# Varela-Logical_EPS_v_1_0.net
KiCad netlist of a schematic drawn in EAGLE
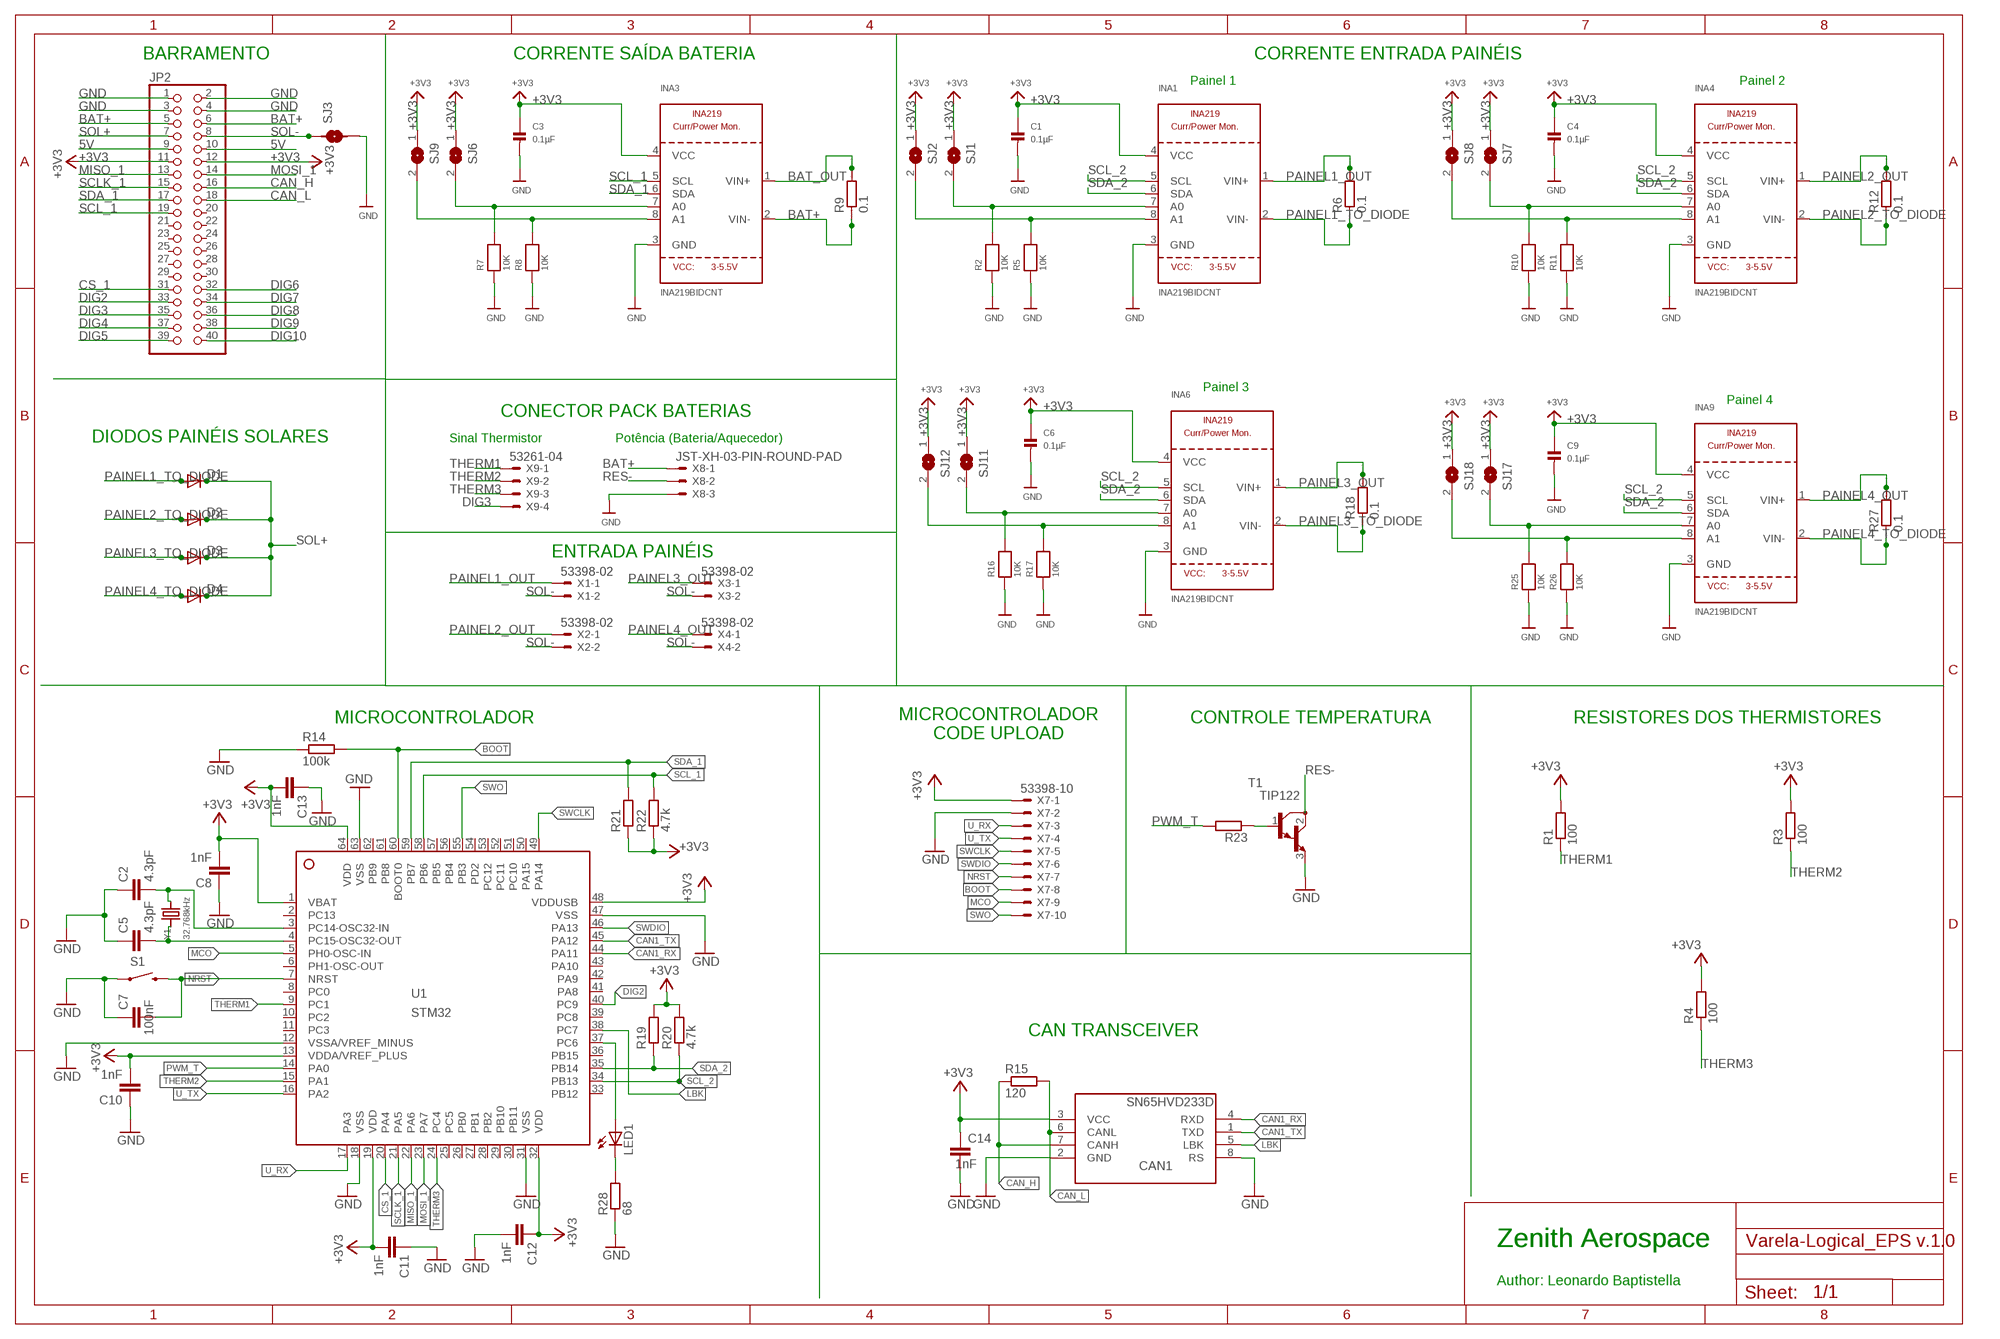
[diagram p0: schematic, sheet 1]

(export (version "E")
  (design (tool "Eeschema 10.0.6"))
  (components
    (comp (ref "C1")
      (value "0.1µF")
      (footprint "eagle-import:1206")
      (libsource (lib "eagle-import") (part "CAP_CERAMIC1206"))
    )
    (comp (ref "C2")
      (value "4.3pF")
      (footprint "eagle-import:C1206")
      (libsource (lib "eagle-import") (part "C-EUC1206"))
    )
    (comp (ref "C3")
      (value "0.1µF")
      (footprint "eagle-import:1206")
      (libsource (lib "eagle-import") (part "CAP_CERAMIC1206"))
    )
    (comp (ref "C4")
      (value "0.1µF")
      (footprint "eagle-import:1206")
      (libsource (lib "eagle-import") (part "CAP_CERAMIC1206"))
    )
    (comp (ref "C5")
      (value "4.3pF")
      (footprint "eagle-import:C1206")
      (libsource (lib "eagle-import") (part "C-EUC1206"))
    )
    (comp (ref "C6")
      (value "0.1µF")
      (footprint "eagle-import:1206")
      (libsource (lib "eagle-import") (part "CAP_CERAMIC1206"))
    )
    (comp (ref "C7")
      (value "100nF")
      (footprint "eagle-import:C1206")
      (libsource (lib "eagle-import") (part "C-EUC1206"))
    )
    (comp (ref "C8")
      (value "1nF")
      (footprint "eagle-import:C1206")
      (libsource (lib "eagle-import") (part "C-EUC1206"))
    )
    (comp (ref "C9")
      (value "0.1µF")
      (footprint "eagle-import:1206")
      (libsource (lib "eagle-import") (part "CAP_CERAMIC1206"))
    )
    (comp (ref "C10")
      (value "1nF")
      (footprint "eagle-import:C1206")
      (libsource (lib "eagle-import") (part "C-EUC1206"))
    )
    (comp (ref "C11")
      (value "1nF")
      (footprint "eagle-import:C1206")
      (libsource (lib "eagle-import") (part "C-EUC1206"))
    )
    (comp (ref "C12")
      (value "1nF")
      (footprint "eagle-import:C1206")
      (libsource (lib "eagle-import") (part "C-EUC1206"))
    )
    (comp (ref "C13")
      (value "1nF")
      (footprint "eagle-import:C1206")
      (libsource (lib "eagle-import") (part "C-EUC1206"))
    )
    (comp (ref "C14")
      (value "1nF")
      (footprint "eagle-import:C1206")
      (libsource (lib "eagle-import") (part "C-EUC1206"))
    )
    (comp (ref "CAN1")
      (value "SN65HVD233D")
      (footprint "eagle-import:SOIC8")
      (fields (field (name "MF") "Texas Instruments"))
      (libsource (lib "eagle-import") (part "SN65HVD233D"))
    )
    (comp (ref "D1")
      (value "DIODE-DO-214AC")
      (footprint "eagle-import:DO-214AC")
      (libsource (lib "eagle-import") (part "DIODE-DO-214AC"))
    )
    (comp (ref "D2")
      (value "DIODE-DO-214AC")
      (footprint "eagle-import:DO-214AC")
      (libsource (lib "eagle-import") (part "DIODE-DO-214AC"))
    )
    (comp (ref "D3")
      (value "DIODE-DO-214AC")
      (footprint "eagle-import:DO-214AC")
      (libsource (lib "eagle-import") (part "DIODE-DO-214AC"))
    )
    (comp (ref "D4")
      (value "DIODE-DO-214AC")
      (footprint "eagle-import:DO-214AC")
      (libsource (lib "eagle-import") (part "DIODE-DO-214AC"))
    )
    (comp (ref "INA1")
      (value "INA219BIDCNT")
      (footprint "eagle-import:SOT23-8")
      (libsource (lib "eagle-import") (part "INA219"))
    )
    (comp (ref "INA3")
      (value "INA219BIDCNT")
      (footprint "eagle-import:SOT23-8")
      (libsource (lib "eagle-import") (part "INA219"))
    )
    (comp (ref "INA4")
      (value "INA219BIDCNT")
      (footprint "eagle-import:SOT23-8")
      (libsource (lib "eagle-import") (part "INA219"))
    )
    (comp (ref "INA6")
      (value "INA219BIDCNT")
      (footprint "eagle-import:SOT23-8")
      (libsource (lib "eagle-import") (part "INA219"))
    )
    (comp (ref "INA9")
      (value "INA219BIDCNT")
      (footprint "eagle-import:SOT23-8")
      (libsource (lib "eagle-import") (part "INA219"))
    )
    (comp (ref "JP2")
      (value "PINHD-2X20")
      (footprint "eagle-import:2X20")
      (libsource (lib "eagle-import") (part "PINHD-2X20"))
    )
    (comp (ref "LED1")
      (value "LEDSMT1206")
      (footprint "eagle-import:1206")
      (libsource (lib "eagle-import") (part "LEDSMT1206"))
    )
    (comp (ref "R1")
      (value "100")
      (footprint "eagle-import:R1206")
      (libsource (lib "eagle-import") (part "R-EU_R1206"))
    )
    (comp (ref "R2")
      (value "10K")
      (footprint "eagle-import:1206")
      (libsource (lib "eagle-import") (part "RESISTOR1206"))
    )
    (comp (ref "R3")
      (value "100")
      (footprint "eagle-import:R1206")
      (libsource (lib "eagle-import") (part "R-EU_R1206"))
    )
    (comp (ref "R4")
      (value "100")
      (footprint "eagle-import:R1206")
      (libsource (lib "eagle-import") (part "R-EU_R1206"))
    )
    (comp (ref "R5")
      (value "10K")
      (footprint "eagle-import:1206")
      (libsource (lib "eagle-import") (part "RESISTOR1206"))
    )
    (comp (ref "R6")
      (value "0.1")
      (footprint "eagle-import:R2512")
      (libsource (lib "eagle-import") (part "RR2512"))
    )
    (comp (ref "R7")
      (value "10K")
      (footprint "eagle-import:1206")
      (libsource (lib "eagle-import") (part "RESISTOR1206"))
    )
    (comp (ref "R8")
      (value "10K")
      (footprint "eagle-import:1206")
      (libsource (lib "eagle-import") (part "RESISTOR1206"))
    )
    (comp (ref "R9")
      (value "0.1")
      (footprint "eagle-import:R2512")
      (libsource (lib "eagle-import") (part "RR2512"))
    )
    (comp (ref "R10")
      (value "10K")
      (footprint "eagle-import:1206")
      (libsource (lib "eagle-import") (part "RESISTOR1206"))
    )
    (comp (ref "R11")
      (value "10K")
      (footprint "eagle-import:1206")
      (libsource (lib "eagle-import") (part "RESISTOR1206"))
    )
    (comp (ref "R12")
      (value "0.1")
      (footprint "eagle-import:R2512")
      (libsource (lib "eagle-import") (part "RR2512"))
    )
    (comp (ref "R14")
      (value "100k")
      (footprint "eagle-import:R1206")
      (libsource (lib "eagle-import") (part "R-EU_R1206"))
    )
    (comp (ref "R15")
      (value "120")
      (footprint "eagle-import:R1206")
      (libsource (lib "eagle-import") (part "R-EU_R1206"))
    )
    (comp (ref "R16")
      (value "10K")
      (footprint "eagle-import:1206")
      (libsource (lib "eagle-import") (part "RESISTOR1206"))
    )
    (comp (ref "R17")
      (value "10K")
      (footprint "eagle-import:1206")
      (libsource (lib "eagle-import") (part "RESISTOR1206"))
    )
    (comp (ref "R18")
      (value "0.1")
      (footprint "eagle-import:R2512")
      (libsource (lib "eagle-import") (part "RR2512"))
    )
    (comp (ref "R19")
      (value "4.7k")
      (footprint "eagle-import:R1206")
      (libsource (lib "eagle-import") (part "R-EU_R1206"))
    )
    (comp (ref "R20")
      (value "4.7k")
      (footprint "eagle-import:R1206")
      (libsource (lib "eagle-import") (part "R-EU_R1206"))
    )
    (comp (ref "R21")
      (value "4.7k")
      (footprint "eagle-import:R1206")
      (libsource (lib "eagle-import") (part "R-EU_R1206"))
    )
    (comp (ref "R22")
      (value "4.7k")
      (footprint "eagle-import:R1206")
      (libsource (lib "eagle-import") (part "R-EU_R1206"))
    )
    (comp (ref "R23")
      (value "R-EU_R1206")
      (footprint "eagle-import:R1206")
      (libsource (lib "eagle-import") (part "R-EU_R1206"))
    )
    (comp (ref "R25")
      (value "10K")
      (footprint "eagle-import:1206")
      (libsource (lib "eagle-import") (part "RESISTOR1206"))
    )
    (comp (ref "R26")
      (value "10K")
      (footprint "eagle-import:1206")
      (libsource (lib "eagle-import") (part "RESISTOR1206"))
    )
    (comp (ref "R27")
      (value "0.1")
      (footprint "eagle-import:R2512")
      (libsource (lib "eagle-import") (part "RR2512"))
    )
    (comp (ref "R28")
      (value "68")
      (footprint "eagle-import:R1206")
      (libsource (lib "eagle-import") (part "R-EU_R1206"))
    )
    (comp (ref "S1")
      (value "SWITCH-MOMENTARY-2SMD-1101NE")
      (footprint "eagle-import:TACTILE-SWITCH-1101NE")
      (libsource (lib "eagle-import") (part "SWITCH-MOMENTARY-2SMD-1101NE"))
    )
    (comp (ref "SJ1")
      (value "SOLDERJUMPERREFLOW_NOPASTE")
      (footprint "eagle-import:SOLDERJUMPER_REFLOW_NOPASTE")
      (libsource (lib "eagle-import") (part "SOLDERJUMPERREFLOW_NOPASTE"))
    )
    (comp (ref "SJ2")
      (value "SOLDERJUMPERREFLOW_NOPASTE")
      (footprint "eagle-import:SOLDERJUMPER_REFLOW_NOPASTE")
      (libsource (lib "eagle-import") (part "SOLDERJUMPERREFLOW_NOPASTE"))
    )
    (comp (ref "SJ3")
      (value "SMD-JUMPER-2")
      (footprint "eagle-import:SMD-JUMPER-2")
      (libsource (lib "eagle-import") (part "SMD-JUMPER-2"))
    )
    (comp (ref "SJ6")
      (value "SOLDERJUMPERREFLOW_NOPASTE")
      (footprint "eagle-import:SOLDERJUMPER_REFLOW_NOPASTE")
      (libsource (lib "eagle-import") (part "SOLDERJUMPERREFLOW_NOPASTE"))
    )
    (comp (ref "SJ7")
      (value "SOLDERJUMPERREFLOW_NOPASTE")
      (footprint "eagle-import:SOLDERJUMPER_REFLOW_NOPASTE")
      (libsource (lib "eagle-import") (part "SOLDERJUMPERREFLOW_NOPASTE"))
    )
    (comp (ref "SJ8")
      (value "SOLDERJUMPERREFLOW_NOPASTE")
      (footprint "eagle-import:SOLDERJUMPER_REFLOW_NOPASTE")
      (libsource (lib "eagle-import") (part "SOLDERJUMPERREFLOW_NOPASTE"))
    )
    (comp (ref "SJ9")
      (value "SOLDERJUMPERREFLOW_NOPASTE")
      (footprint "eagle-import:SOLDERJUMPER_REFLOW_NOPASTE")
      (libsource (lib "eagle-import") (part "SOLDERJUMPERREFLOW_NOPASTE"))
    )
    (comp (ref "SJ11")
      (value "SOLDERJUMPERREFLOW_NOPASTE")
      (footprint "eagle-import:SOLDERJUMPER_REFLOW_NOPASTE")
      (libsource (lib "eagle-import") (part "SOLDERJUMPERREFLOW_NOPASTE"))
    )
    (comp (ref "SJ12")
      (value "SOLDERJUMPERREFLOW_NOPASTE")
      (footprint "eagle-import:SOLDERJUMPER_REFLOW_NOPASTE")
      (libsource (lib "eagle-import") (part "SOLDERJUMPERREFLOW_NOPASTE"))
    )
    (comp (ref "SJ17")
      (value "SOLDERJUMPERREFLOW_NOPASTE")
      (footprint "eagle-import:SOLDERJUMPER_REFLOW_NOPASTE")
      (libsource (lib "eagle-import") (part "SOLDERJUMPERREFLOW_NOPASTE"))
    )
    (comp (ref "SJ18")
      (value "SOLDERJUMPERREFLOW_NOPASTE")
      (footprint "eagle-import:SOLDERJUMPER_REFLOW_NOPASTE")
      (libsource (lib "eagle-import") (part "SOLDERJUMPERREFLOW_NOPASTE"))
    )
    (comp (ref "T1")
      (value "TIP122")
      (footprint "eagle-import:TO220")
      (libsource (lib "eagle-import") (part "TIP122"))
    )
    (comp (ref "U1")
      (value "STM32")
      (footprint "eagle-import:LQFP64_10X10")
      (libsource (lib "eagle-import") (part "STM32L476RCT6"))
    )
    (comp (ref "X1")
      (value "53398-02")
      (footprint "eagle-import:53398-02")
      (fields (field (name "MF") "MOLEX"))
      (libsource (lib "eagle-import") (part "53?-02398"))
    )
    (comp (ref "X2")
      (value "53398-02")
      (footprint "eagle-import:53398-02")
      (fields (field (name "MF") "MOLEX"))
      (libsource (lib "eagle-import") (part "53?-02398"))
    )
    (comp (ref "X3")
      (value "53398-02")
      (footprint "eagle-import:53398-02")
      (fields (field (name "MF") "MOLEX"))
      (libsource (lib "eagle-import") (part "53?-02398"))
    )
    (comp (ref "X4")
      (value "53398-02")
      (footprint "eagle-import:53398-02")
      (fields (field (name "MF") "MOLEX"))
      (libsource (lib "eagle-import") (part "53?-02398"))
    )
    (comp (ref "X7")
      (value "53398-10")
      (footprint "eagle-import:53398-10")
      (fields (field (name "MF") "MOLEX") (field (name "MPN") "53398-1071"))
      (libsource (lib "eagle-import") (part "53?-10398"))
    )
    (comp (ref "X8")
      (value "JST-XH-03-PIN-ROUND-PAD")
      (footprint "eagle-import:JST-XH-03-PACKAGE-ROUND-PAD")
      (libsource (lib "eagle-import") (part "JST-XH-03-PIN-ROUND-PAD"))
    )
    (comp (ref "X9")
      (value "53261-04")
      (footprint "eagle-import:53261-04")
      (fields (field (name "MF") "MOLEX"))
      (libsource (lib "eagle-import") (part "53?-04261"))
    )
    (comp (ref "Y1")
      (value "32.768kHz")
      (footprint "eagle-import:CRYSTAL_8X3.8")
      (libsource (lib "eagle-import") (part "CRYSTAL8X3.8SMT"))
    )
  )
  (nets
    (net (code "1") (name "+3V3") (class "Default")
      (node (ref "C1") (pin "1") (pinfunction "P$1_1") (pintype "passive"))
      (node (ref "C10") (pin "2") (pinfunction "2_2") (pintype "passive"))
      (node (ref "C11") (pin "2") (pinfunction "2_2") (pintype "passive"))
      (node (ref "C12") (pin "1") (pinfunction "1_1") (pintype "passive"))
      (node (ref "C13") (pin "2") (pinfunction "2_2") (pintype "passive"))
      (node (ref "C14") (pin "1") (pinfunction "1_1") (pintype "passive"))
      (node (ref "C3") (pin "1") (pinfunction "P$1_1") (pintype "passive"))
      (node (ref "C4") (pin "1") (pinfunction "P$1_1") (pintype "passive"))
      (node (ref "C6") (pin "1") (pinfunction "P$1_1") (pintype "passive"))
      (node (ref "C8") (pin "2") (pinfunction "2_2") (pintype "passive"))
      (node (ref "C9") (pin "1") (pinfunction "P$1_1") (pintype "passive"))
      (node (ref "CAN1") (pin "3") (pinfunction "VCC_3") (pintype "power_in"))
      (node (ref "INA1") (pin "4") (pinfunction "VCC_4") (pintype "bidirectional"))
      (node (ref "INA3") (pin "4") (pinfunction "VCC_4") (pintype "bidirectional"))
      (node (ref "INA4") (pin "4") (pinfunction "VCC_4") (pintype "bidirectional"))
      (node (ref "INA6") (pin "4") (pinfunction "VCC_4") (pintype "bidirectional"))
      (node (ref "INA9") (pin "4") (pinfunction "VCC_4") (pintype "bidirectional"))
      (node (ref "JP2") (pin "11") (pinfunction "11_11") (pintype "passive"))
      (node (ref "JP2") (pin "12") (pinfunction "12_12") (pintype "passive"))
      (node (ref "R1") (pin "2") (pinfunction "2_2") (pintype "passive"))
      (node (ref "R19") (pin "2") (pinfunction "2_2") (pintype "passive"))
      (node (ref "R20") (pin "2") (pinfunction "2_2") (pintype "passive"))
      (node (ref "R21") (pin "1") (pinfunction "1_1") (pintype "passive"))
      (node (ref "R22") (pin "1") (pinfunction "1_1") (pintype "passive"))
      (node (ref "R3") (pin "2") (pinfunction "2_2") (pintype "passive"))
      (node (ref "R4") (pin "2") (pinfunction "2_2") (pintype "passive"))
      (node (ref "SJ1") (pin "1") (pinfunction "1_1") (pintype "passive"))
      (node (ref "SJ11") (pin "1") (pinfunction "1_1") (pintype "passive"))
      (node (ref "SJ12") (pin "1") (pinfunction "1_1") (pintype "passive"))
      (node (ref "SJ17") (pin "1") (pinfunction "1_1") (pintype "passive"))
      (node (ref "SJ18") (pin "1") (pinfunction "1_1") (pintype "passive"))
      (node (ref "SJ2") (pin "1") (pinfunction "1_1") (pintype "passive"))
      (node (ref "SJ6") (pin "1") (pinfunction "1_1") (pintype "passive"))
      (node (ref "SJ7") (pin "1") (pinfunction "1_1") (pintype "passive"))
      (node (ref "SJ8") (pin "1") (pinfunction "1_1") (pintype "passive"))
      (node (ref "SJ9") (pin "1") (pinfunction "1_1") (pintype "passive"))
      (node (ref "U1") (pin "1") (pinfunction "VBAT_1") (pintype "passive"))
      (node (ref "U1") (pin "13") (pinfunction "VDDA/VREF_PLUS_13") (pintype "passive"))
      (node (ref "U1") (pin "19") (pinfunction "VDD_19") (pintype "power_in"))
      (node (ref "U1") (pin "32") (pinfunction "VDD_32") (pintype "power_in"))
      (node (ref "U1") (pin "48") (pinfunction "VDDUSB_48") (pintype "bidirectional"))
      (node (ref "U1") (pin "64") (pinfunction "VDD_64") (pintype "power_in"))
      (node (ref "X7") (pin "1") (pinfunction "S_1") (pintype "passive"))
    )
    (net (code "2") (name "/5V") (class "Default")
      (node (ref "JP2") (pin "10") (pinfunction "10_10") (pintype "passive"))
      (node (ref "JP2") (pin "9") (pinfunction "9_9") (pintype "passive"))
    )
    (net (code "3") (name "/BAT+") (class "Default")
      (node (ref "INA3") (pin "2") (pinfunction "VIN-_2") (pintype "bidirectional"))
      (node (ref "JP2") (pin "5") (pinfunction "5_5") (pintype "passive"))
      (node (ref "JP2") (pin "6") (pinfunction "6_6") (pintype "passive"))
      (node (ref "R9") (pin "1") (pinfunction "1_1") (pintype "passive"))
      (node (ref "X8") (pin "1") (pinfunction "S_1") (pintype "passive"))
    )
    (net (code "4") (name "/BAT_OUT") (class "Default")
      (node (ref "INA3") (pin "1") (pinfunction "VIN+_1") (pintype "bidirectional"))
      (node (ref "R9") (pin "2") (pinfunction "2_2") (pintype "passive"))
    )
    (net (code "5") (name "/DIG3") (class "Default")
      (node (ref "JP2") (pin "35") (pinfunction "35_35") (pintype "passive"))
      (node (ref "X9") (pin "4") (pinfunction "S_4") (pintype "passive"))
    )
    (net (code "6") (name "/DIG4") (class "Default")
      (node (ref "JP2") (pin "37") (pinfunction "37_37") (pintype "passive"))
    )
    (net (code "7") (name "/DIG5") (class "Default")
      (node (ref "JP2") (pin "39") (pinfunction "39_39") (pintype "passive"))
    )
    (net (code "8") (name "/DIG6") (class "Default")
      (node (ref "JP2") (pin "32") (pinfunction "32_32") (pintype "passive"))
    )
    (net (code "9") (name "/DIG7") (class "Default")
      (node (ref "JP2") (pin "34") (pinfunction "34_34") (pintype "passive"))
    )
    (net (code "10") (name "/DIG8") (class "Default")
      (node (ref "JP2") (pin "36") (pinfunction "36_36") (pintype "passive"))
    )
    (net (code "11") (name "/DIG9") (class "Default")
      (node (ref "JP2") (pin "38") (pinfunction "38_38") (pintype "passive"))
    )
    (net (code "12") (name "/DIG10") (class "Default")
      (node (ref "JP2") (pin "40") (pinfunction "40_40") (pintype "passive"))
    )
    (net (code "13") (name "/PAINEL1_OUT") (class "Default")
      (node (ref "INA1") (pin "1") (pinfunction "VIN+_1") (pintype "bidirectional"))
      (node (ref "R6") (pin "2") (pinfunction "2_2") (pintype "passive"))
      (node (ref "X1") (pin "1") (pinfunction "S_1") (pintype "passive"))
    )
    (net (code "14") (name "/PAINEL1_TO_DIODE") (class "Default")
      (node (ref "D1") (pin "A") (pinfunction "A_A") (pintype "passive"))
      (node (ref "INA1") (pin "2") (pinfunction "VIN-_2") (pintype "bidirectional"))
      (node (ref "R6") (pin "1") (pinfunction "1_1") (pintype "passive"))
    )
    (net (code "15") (name "/PAINEL2_OUT") (class "Default")
      (node (ref "INA4") (pin "1") (pinfunction "VIN+_1") (pintype "bidirectional"))
      (node (ref "R12") (pin "2") (pinfunction "2_2") (pintype "passive"))
      (node (ref "X2") (pin "1") (pinfunction "S_1") (pintype "passive"))
    )
    (net (code "16") (name "/PAINEL2_TO_DIODE") (class "Default")
      (node (ref "D2") (pin "A") (pinfunction "A_A") (pintype "passive"))
      (node (ref "INA4") (pin "2") (pinfunction "VIN-_2") (pintype "bidirectional"))
      (node (ref "R12") (pin "1") (pinfunction "1_1") (pintype "passive"))
    )
    (net (code "17") (name "/PAINEL3_OUT") (class "Default")
      (node (ref "INA6") (pin "1") (pinfunction "VIN+_1") (pintype "bidirectional"))
      (node (ref "R18") (pin "2") (pinfunction "2_2") (pintype "passive"))
      (node (ref "X3") (pin "1") (pinfunction "S_1") (pintype "passive"))
    )
    (net (code "18") (name "/PAINEL3_TO_DIODE") (class "Default")
      (node (ref "D3") (pin "A") (pinfunction "A_A") (pintype "passive"))
      (node (ref "INA6") (pin "2") (pinfunction "VIN-_2") (pintype "bidirectional"))
      (node (ref "R18") (pin "1") (pinfunction "1_1") (pintype "passive"))
    )
    (net (code "19") (name "/PAINEL4_OUT") (class "Default")
      (node (ref "INA9") (pin "1") (pinfunction "VIN+_1") (pintype "bidirectional"))
      (node (ref "R27") (pin "2") (pinfunction "2_2") (pintype "passive"))
      (node (ref "X4") (pin "1") (pinfunction "S_1") (pintype "passive"))
    )
    (net (code "20") (name "/PAINEL4_TO_DIODE") (class "Default")
      (node (ref "D4") (pin "A") (pinfunction "A_A") (pintype "passive"))
      (node (ref "INA9") (pin "2") (pinfunction "VIN-_2") (pintype "bidirectional"))
      (node (ref "R27") (pin "1") (pinfunction "1_1") (pintype "passive"))
    )
    (net (code "21") (name "/RES-") (class "Default")
      (node (ref "T1") (pin "2") (pinfunction "C_2") (pintype "passive"))
      (node (ref "X8") (pin "2") (pinfunction "S_2") (pintype "passive"))
    )
    (net (code "22") (name "/SOL+") (class "Default")
      (node (ref "D1") (pin "C") (pinfunction "C_C") (pintype "passive"))
      (node (ref "D2") (pin "C") (pinfunction "C_C") (pintype "passive"))
      (node (ref "D3") (pin "C") (pinfunction "C_C") (pintype "passive"))
      (node (ref "D4") (pin "C") (pinfunction "C_C") (pintype "passive"))
      (node (ref "JP2") (pin "7") (pinfunction "7_7") (pintype "passive"))
    )
    (net (code "23") (name "/SOL-") (class "Default")
      (node (ref "JP2") (pin "8") (pinfunction "8_8") (pintype "passive"))
      (node (ref "SJ3") (pin "1") (pinfunction "1_1") (pintype "passive"))
      (node (ref "X1") (pin "2") (pinfunction "S_2") (pintype "passive"))
      (node (ref "X2") (pin "2") (pinfunction "S_2") (pintype "passive"))
      (node (ref "X3") (pin "2") (pinfunction "S_2") (pintype "passive"))
      (node (ref "X4") (pin "2") (pinfunction "S_2") (pintype "passive"))
    )
    (net (code "24") (name "BOOT") (class "Default")
      (node (ref "R14") (pin "2") (pinfunction "2_2") (pintype "passive"))
      (node (ref "U1") (pin "60") (pinfunction "BOOT0_60") (pintype "input"))
      (node (ref "X7") (pin "8") (pinfunction "S_8") (pintype "passive"))
    )
    (net (code "25") (name "CAN1_RX") (class "Default")
      (node (ref "CAN1") (pin "4") (pinfunction "RXD_4") (pintype "output"))
      (node (ref "U1") (pin "44") (pinfunction "PA11_44") (pintype "bidirectional"))
    )
    (net (code "26") (name "CAN1_TX") (class "Default")
      (node (ref "CAN1") (pin "1") (pinfunction "TXD_1") (pintype "bidirectional"))
      (node (ref "U1") (pin "45") (pinfunction "PA12_45") (pintype "bidirectional"))
    )
    (net (code "27") (name "CAN_H") (class "Default")
      (node (ref "CAN1") (pin "7") (pinfunction "CANH_7") (pintype "bidirectional"))
      (node (ref "JP2") (pin "16") (pinfunction "16_16") (pintype "passive"))
      (node (ref "R15") (pin "1") (pinfunction "1_1") (pintype "passive"))
    )
    (net (code "28") (name "CAN_L") (class "Default")
      (node (ref "CAN1") (pin "6") (pinfunction "CANL_6") (pintype "bidirectional"))
      (node (ref "JP2") (pin "18") (pinfunction "18_18") (pintype "passive"))
      (node (ref "R15") (pin "2") (pinfunction "2_2") (pintype "passive"))
    )
    (net (code "29") (name "CS_1") (class "Default")
      (node (ref "JP2") (pin "31") (pinfunction "31_31") (pintype "passive"))
      (node (ref "U1") (pin "20") (pinfunction "PA4_20") (pintype "bidirectional"))
    )
    (net (code "30") (name "DIG2") (class "Default")
      (node (ref "JP2") (pin "33") (pinfunction "33_33") (pintype "passive"))
      (node (ref "U1") (pin "40") (pinfunction "PC9_40") (pintype "bidirectional"))
    )
    (net (code "31") (name "GND") (class "Default")
      (node (ref "C1") (pin "2") (pinfunction "P$2_2") (pintype "passive"))
      (node (ref "C10") (pin "1") (pinfunction "1_1") (pintype "passive"))
      (node (ref "C11") (pin "1") (pinfunction "1_1") (pintype "passive"))
      (node (ref "C12") (pin "2") (pinfunction "2_2") (pintype "passive"))
      (node (ref "C13") (pin "1") (pinfunction "1_1") (pintype "passive"))
      (node (ref "C14") (pin "2") (pinfunction "2_2") (pintype "passive"))
      (node (ref "C2") (pin "1") (pinfunction "1_1") (pintype "passive"))
      (node (ref "C3") (pin "2") (pinfunction "P$2_2") (pintype "passive"))
      (node (ref "C4") (pin "2") (pinfunction "P$2_2") (pintype "passive"))
      (node (ref "C5") (pin "1") (pinfunction "1_1") (pintype "passive"))
      (node (ref "C6") (pin "2") (pinfunction "P$2_2") (pintype "passive"))
      (node (ref "C7") (pin "1") (pinfunction "1_1") (pintype "passive"))
      (node (ref "C8") (pin "1") (pinfunction "1_1") (pintype "passive"))
      (node (ref "C9") (pin "2") (pinfunction "P$2_2") (pintype "passive"))
      (node (ref "CAN1") (pin "2") (pinfunction "GND_2") (pintype "power_in"))
      (node (ref "CAN1") (pin "8") (pinfunction "RS_8") (pintype "input"))
      (node (ref "INA1") (pin "3") (pinfunction "GND_3") (pintype "bidirectional"))
      (node (ref "INA3") (pin "3") (pinfunction "GND_3") (pintype "bidirectional"))
      (node (ref "INA4") (pin "3") (pinfunction "GND_3") (pintype "bidirectional"))
      (node (ref "INA6") (pin "3") (pinfunction "GND_3") (pintype "bidirectional"))
      (node (ref "INA9") (pin "3") (pinfunction "GND_3") (pintype "bidirectional"))
      (node (ref "JP2") (pin "1") (pinfunction "1_1") (pintype "passive"))
      (node (ref "JP2") (pin "2") (pinfunction "2_2") (pintype "passive"))
      (node (ref "JP2") (pin "3") (pinfunction "3_3") (pintype "passive"))
      (node (ref "JP2") (pin "4") (pinfunction "4_4") (pintype "passive"))
      (node (ref "R10") (pin "1") (pinfunction "1_1") (pintype "passive"))
      (node (ref "R11") (pin "1") (pinfunction "1_1") (pintype "passive"))
      (node (ref "R14") (pin "1") (pinfunction "1_1") (pintype "passive"))
      (node (ref "R16") (pin "1") (pinfunction "1_1") (pintype "passive"))
      (node (ref "R17") (pin "1") (pinfunction "1_1") (pintype "passive"))
      (node (ref "R2") (pin "1") (pinfunction "1_1") (pintype "passive"))
      (node (ref "R25") (pin "1") (pinfunction "1_1") (pintype "passive"))
      (node (ref "R26") (pin "1") (pinfunction "1_1") (pintype "passive"))
      (node (ref "R28") (pin "1") (pinfunction "1_1") (pintype "passive"))
      (node (ref "R5") (pin "1") (pinfunction "1_1") (pintype "passive"))
      (node (ref "R7") (pin "1") (pinfunction "1_1") (pintype "passive"))
      (node (ref "R8") (pin "1") (pinfunction "1_1") (pintype "passive"))
      (node (ref "S1") (pin "1") (pinfunction "1_1") (pintype "passive"))
      (node (ref "SJ3") (pin "2") (pinfunction "2_2") (pintype "passive"))
      (node (ref "T1") (pin "3") (pinfunction "E_3") (pintype "passive"))
      (node (ref "U1") (pin "12") (pinfunction "VSSA/VREF_MINUS_12") (pintype "passive"))
      (node (ref "U1") (pin "18") (pinfunction "VSS_18") (pintype "power_in"))
      (node (ref "U1") (pin "31") (pinfunction "VSS_31") (pintype "power_in"))
      (node (ref "U1") (pin "47") (pinfunction "VSS_47") (pintype "power_in"))
      (node (ref "U1") (pin "63") (pinfunction "VSS_63") (pintype "power_in"))
      (node (ref "X7") (pin "2") (pinfunction "S_2") (pintype "passive"))
      (node (ref "X8") (pin "3") (pinfunction "S_3") (pintype "passive"))
    )
    (net (code "32") (name "LBK") (class "Default")
      (node (ref "CAN1") (pin "5") (pinfunction "LBK_5") (pintype "output"))
      (node (ref "U1") (pin "38") (pinfunction "PC7_38") (pintype "bidirectional"))
    )
    (net (code "33") (name "MCO") (class "Default")
      (node (ref "U1") (pin "5") (pinfunction "PH0-OSC-IN_5") (pintype "bidirectional"))
      (node (ref "X7") (pin "9") (pinfunction "S_9") (pintype "passive"))
    )
    (net (code "34") (name "MISO_1") (class "Default")
      (node (ref "JP2") (pin "13") (pinfunction "13_13") (pintype "passive"))
      (node (ref "U1") (pin "22") (pinfunction "PA6_22") (pintype "bidirectional"))
    )
    (net (code "35") (name "MOSI_1") (class "Default")
      (node (ref "JP2") (pin "14") (pinfunction "14_14") (pintype "passive"))
      (node (ref "U1") (pin "23") (pinfunction "PA7_23") (pintype "bidirectional"))
    )
    (net (code "36") (name "NRST") (class "Default")
      (node (ref "C7") (pin "2") (pinfunction "2_2") (pintype "passive"))
      (node (ref "S1") (pin "2") (pinfunction "2_2") (pintype "passive"))
      (node (ref "U1") (pin "7") (pinfunction "NRST_7") (pintype "input"))
      (node (ref "X7") (pin "7") (pinfunction "S_7") (pintype "passive"))
    )
    (net (code "37") (name "Net-(INA1-A0)") (class "Default")
      (node (ref "INA1") (pin "7") (pinfunction "A0_7") (pintype "bidirectional"))
      (node (ref "R2") (pin "2") (pinfunction "2_2") (pintype "passive"))
      (node (ref "SJ1") (pin "2") (pinfunction "2_2") (pintype "passive"))
    )
    (net (code "38") (name "Net-(INA1-A1)") (class "Default")
      (node (ref "INA1") (pin "8") (pinfunction "A1_8") (pintype "bidirectional"))
      (node (ref "R5") (pin "2") (pinfunction "2_2") (pintype "passive"))
      (node (ref "SJ2") (pin "2") (pinfunction "2_2") (pintype "passive"))
    )
    (net (code "39") (name "Net-(INA3-A0)") (class "Default")
      (node (ref "INA3") (pin "7") (pinfunction "A0_7") (pintype "bidirectional"))
      (node (ref "R7") (pin "2") (pinfunction "2_2") (pintype "passive"))
      (node (ref "SJ6") (pin "2") (pinfunction "2_2") (pintype "passive"))
    )
    (net (code "40") (name "Net-(INA3-A1)") (class "Default")
      (node (ref "INA3") (pin "8") (pinfunction "A1_8") (pintype "bidirectional"))
      (node (ref "R8") (pin "2") (pinfunction "2_2") (pintype "passive"))
      (node (ref "SJ9") (pin "2") (pinfunction "2_2") (pintype "passive"))
    )
    (net (code "41") (name "Net-(INA4-A0)") (class "Default")
      (node (ref "INA4") (pin "7") (pinfunction "A0_7") (pintype "bidirectional"))
      (node (ref "R10") (pin "2") (pinfunction "2_2") (pintype "passive"))
      (node (ref "SJ7") (pin "2") (pinfunction "2_2") (pintype "passive"))
    )
    (net (code "42") (name "Net-(INA4-A1)") (class "Default")
      (node (ref "INA4") (pin "8") (pinfunction "A1_8") (pintype "bidirectional"))
      (node (ref "R11") (pin "2") (pinfunction "2_2") (pintype "passive"))
      (node (ref "SJ8") (pin "2") (pinfunction "2_2") (pintype "passive"))
    )
    (net (code "43") (name "Net-(INA6-A0)") (class "Default")
      (node (ref "INA6") (pin "7") (pinfunction "A0_7") (pintype "bidirectional"))
      (node (ref "R16") (pin "2") (pinfunction "2_2") (pintype "passive"))
      (node (ref "SJ11") (pin "2") (pinfunction "2_2") (pintype "passive"))
    )
    (net (code "44") (name "Net-(INA6-A1)") (class "Default")
      (node (ref "INA6") (pin "8") (pinfunction "A1_8") (pintype "bidirectional"))
      (node (ref "R17") (pin "2") (pinfunction "2_2") (pintype "passive"))
      (node (ref "SJ12") (pin "2") (pinfunction "2_2") (pintype "passive"))
    )
    (net (code "45") (name "Net-(INA9-A0)") (class "Default")
      (node (ref "INA9") (pin "7") (pinfunction "A0_7") (pintype "bidirectional"))
      (node (ref "R25") (pin "2") (pinfunction "2_2") (pintype "passive"))
      (node (ref "SJ17") (pin "2") (pinfunction "2_2") (pintype "passive"))
    )
    (net (code "46") (name "Net-(INA9-A1)") (class "Default")
      (node (ref "INA9") (pin "8") (pinfunction "A1_8") (pintype "bidirectional"))
      (node (ref "R26") (pin "2") (pinfunction "2_2") (pintype "passive"))
      (node (ref "SJ18") (pin "2") (pinfunction "2_2") (pintype "passive"))
    )
    (net (code "47") (name "Net-(LED1-PadC)") (class "Default")
      (node (ref "LED1") (pin "C") (pinfunction "C_C") (pintype "passive"))
      (node (ref "R28") (pin "2") (pinfunction "2_2") (pintype "passive"))
    )
    (net (code "48") (name "Net-(T1-B)") (class "Default")
      (node (ref "R23") (pin "1") (pinfunction "1_1") (pintype "passive"))
      (node (ref "T1") (pin "1") (pinfunction "B_1") (pintype "passive"))
    )
    (net (code "49") (name "Net-(U1-PC6)") (class "Default")
      (node (ref "LED1") (pin "A") (pinfunction "A_A") (pintype "passive"))
      (node (ref "U1") (pin "37") (pinfunction "PC6_37") (pintype "bidirectional"))
    )
    (net (code "50") (name "Net-(U1-PC14-OSC32-IN)") (class "Default")
      (node (ref "C2") (pin "2") (pinfunction "2_2") (pintype "passive"))
      (node (ref "U1") (pin "3") (pinfunction "PC14-OSC32-IN_3") (pintype "bidirectional"))
      (node (ref "Y1") (pin "P$4") (pinfunction "2_P$4") (pintype "passive"))
    )
    (net (code "51") (name "Net-(U1-PC15-OSC32-OUT)") (class "Default")
      (node (ref "C5") (pin "2") (pinfunction "2_2") (pintype "passive"))
      (node (ref "U1") (pin "4") (pinfunction "PC15-OSC32-OUT_4") (pintype "bidirectional"))
      (node (ref "Y1") (pin "P$1") (pinfunction "1_P$1") (pintype "passive"))
    )
    (net (code "52") (name "PWM_T") (class "Default")
      (node (ref "R23") (pin "2") (pinfunction "2_2") (pintype "passive"))
      (node (ref "U1") (pin "14") (pinfunction "PA0_14") (pintype "bidirectional"))
    )
    (net (code "53") (name "SCLK_1") (class "Default")
      (node (ref "JP2") (pin "15") (pinfunction "15_15") (pintype "passive"))
      (node (ref "U1") (pin "21") (pinfunction "PA5_21") (pintype "bidirectional"))
    )
    (net (code "54") (name "SCL_1") (class "Default")
      (node (ref "INA3") (pin "5") (pinfunction "SCL_5") (pintype "bidirectional"))
      (node (ref "JP2") (pin "19") (pinfunction "19_19") (pintype "passive"))
      (node (ref "R22") (pin "2") (pinfunction "2_2") (pintype "passive"))
      (node (ref "U1") (pin "58") (pinfunction "PB6_58") (pintype "bidirectional"))
    )
    (net (code "55") (name "SCL_2") (class "Default")
      (node (ref "INA1") (pin "5") (pinfunction "SCL_5") (pintype "bidirectional"))
      (node (ref "INA4") (pin "5") (pinfunction "SCL_5") (pintype "bidirectional"))
      (node (ref "INA6") (pin "5") (pinfunction "SCL_5") (pintype "bidirectional"))
      (node (ref "INA9") (pin "5") (pinfunction "SCL_5") (pintype "bidirectional"))
      (node (ref "R20") (pin "1") (pinfunction "1_1") (pintype "passive"))
      (node (ref "U1") (pin "34") (pinfunction "PB13_34") (pintype "bidirectional"))
    )
    (net (code "56") (name "SDA_1") (class "Default")
      (node (ref "INA3") (pin "6") (pinfunction "SDA_6") (pintype "bidirectional"))
      (node (ref "JP2") (pin "17") (pinfunction "17_17") (pintype "passive"))
      (node (ref "R21") (pin "2") (pinfunction "2_2") (pintype "passive"))
      (node (ref "U1") (pin "59") (pinfunction "PB7_59") (pintype "bidirectional"))
    )
    (net (code "57") (name "SDA_2") (class "Default")
      (node (ref "INA1") (pin "6") (pinfunction "SDA_6") (pintype "bidirectional"))
      (node (ref "INA4") (pin "6") (pinfunction "SDA_6") (pintype "bidirectional"))
      (node (ref "INA6") (pin "6") (pinfunction "SDA_6") (pintype "bidirectional"))
      (node (ref "INA9") (pin "6") (pinfunction "SDA_6") (pintype "bidirectional"))
      (node (ref "R19") (pin "1") (pinfunction "1_1") (pintype "passive"))
      (node (ref "U1") (pin "35") (pinfunction "PB14_35") (pintype "bidirectional"))
    )
    (net (code "58") (name "SWCLK") (class "Default")
      (node (ref "U1") (pin "49") (pinfunction "PA14_49") (pintype "input"))
      (node (ref "X7") (pin "5") (pinfunction "S_5") (pintype "passive"))
    )
    (net (code "59") (name "SWDIO") (class "Default")
      (node (ref "U1") (pin "46") (pinfunction "PA13_46") (pintype "input"))
      (node (ref "X7") (pin "6") (pinfunction "S_6") (pintype "passive"))
    )
    (net (code "60") (name "SWO") (class "Default")
      (node (ref "U1") (pin "55") (pinfunction "PB3_55") (pintype "output"))
      (node (ref "X7") (pin "10") (pinfunction "S_10") (pintype "passive"))
    )
    (net (code "61") (name "THERM1") (class "Default")
      (node (ref "R1") (pin "1") (pinfunction "1_1") (pintype "passive"))
      (node (ref "U1") (pin "9") (pinfunction "PC1_9") (pintype "bidirectional"))
      (node (ref "X9") (pin "1") (pinfunction "S_1") (pintype "passive"))
    )
    (net (code "62") (name "THERM2") (class "Default")
      (node (ref "R3") (pin "1") (pinfunction "1_1") (pintype "passive"))
      (node (ref "U1") (pin "15") (pinfunction "PA1_15") (pintype "bidirectional"))
      (node (ref "X9") (pin "2") (pinfunction "S_2") (pintype "passive"))
    )
    (net (code "63") (name "THERM3") (class "Default")
      (node (ref "R4") (pin "1") (pinfunction "1_1") (pintype "passive"))
      (node (ref "U1") (pin "24") (pinfunction "PC4_24") (pintype "bidirectional"))
      (node (ref "X9") (pin "3") (pinfunction "S_3") (pintype "passive"))
    )
    (net (code "64") (name "U_RX") (class "Default")
      (node (ref "U1") (pin "17") (pinfunction "PA3_17") (pintype "bidirectional"))
      (node (ref "X7") (pin "3") (pinfunction "S_3") (pintype "passive"))
    )
    (net (code "65") (name "U_TX") (class "Default")
      (node (ref "U1") (pin "16") (pinfunction "PA2_16") (pintype "bidirectional"))
      (node (ref "X7") (pin "4") (pinfunction "S_4") (pintype "passive"))
    )
    (net (code "66") (name "unconnected-(JP2-Pad20)") (class "Default")
      (node (ref "JP2") (pin "20") (pinfunction "20_20") (pintype "passive"))
    )
    (net (code "67") (name "unconnected-(JP2-Pad21)") (class "Default")
      (node (ref "JP2") (pin "21") (pinfunction "21_21") (pintype "passive"))
    )
    (net (code "68") (name "unconnected-(JP2-Pad22)") (class "Default")
      (node (ref "JP2") (pin "22") (pinfunction "22_22") (pintype "passive"))
    )
    (net (code "69") (name "unconnected-(JP2-Pad23)") (class "Default")
      (node (ref "JP2") (pin "23") (pinfunction "23_23") (pintype "passive"))
    )
    (net (code "70") (name "unconnected-(JP2-Pad24)") (class "Default")
      (node (ref "JP2") (pin "24") (pinfunction "24_24") (pintype "passive"))
    )
    (net (code "71") (name "unconnected-(JP2-Pad25)") (class "Default")
      (node (ref "JP2") (pin "25") (pinfunction "25_25") (pintype "passive"))
    )
    (net (code "72") (name "unconnected-(JP2-Pad26)") (class "Default")
      (node (ref "JP2") (pin "26") (pinfunction "26_26") (pintype "passive"))
    )
    (net (code "73") (name "unconnected-(JP2-Pad27)") (class "Default")
      (node (ref "JP2") (pin "27") (pinfunction "27_27") (pintype "passive"))
    )
    (net (code "74") (name "unconnected-(JP2-Pad28)") (class "Default")
      (node (ref "JP2") (pin "28") (pinfunction "28_28") (pintype "passive"))
    )
    (net (code "75") (name "unconnected-(JP2-Pad29)") (class "Default")
      (node (ref "JP2") (pin "29") (pinfunction "29_29") (pintype "passive"))
    )
    (net (code "76") (name "unconnected-(JP2-Pad30)") (class "Default")
      (node (ref "JP2") (pin "30") (pinfunction "30_30") (pintype "passive"))
    )
    (net (code "77") (name "unconnected-(U1-PA8-Pad41)") (class "Default")
      (node (ref "U1") (pin "41") (pinfunction "PA8_41") (pintype "bidirectional"))
    )
    (net (code "78") (name "unconnected-(U1-PA9-Pad42)") (class "Default")
      (node (ref "U1") (pin "42") (pinfunction "PA9_42") (pintype "bidirectional"))
    )
    (net (code "79") (name "unconnected-(U1-PA10-Pad43)") (class "Default")
      (node (ref "U1") (pin "43") (pinfunction "PA10_43") (pintype "bidirectional"))
    )
    (net (code "80") (name "unconnected-(U1-PA15-Pad50)") (class "Default")
      (node (ref "U1") (pin "50") (pinfunction "PA15_50") (pintype "input"))
    )
    (net (code "81") (name "unconnected-(U1-PB0-Pad26)") (class "Default")
      (node (ref "U1") (pin "26") (pinfunction "PB0_26") (pintype "bidirectional"))
    )
    (net (code "82") (name "unconnected-(U1-PB1-Pad27)") (class "Default")
      (node (ref "U1") (pin "27") (pinfunction "PB1_27") (pintype "bidirectional"))
    )
    (net (code "83") (name "unconnected-(U1-PB2-Pad28)") (class "Default")
      (node (ref "U1") (pin "28") (pinfunction "PB2_28") (pintype "bidirectional"))
    )
    (net (code "84") (name "unconnected-(U1-PB4-Pad56)") (class "Default")
      (node (ref "U1") (pin "56") (pinfunction "PB4_56") (pintype "input"))
    )
    (net (code "85") (name "unconnected-(U1-PB5-Pad57)") (class "Default")
      (node (ref "U1") (pin "57") (pinfunction "PB5_57") (pintype "bidirectional"))
    )
    (net (code "86") (name "unconnected-(U1-PB8-Pad61)") (class "Default")
      (node (ref "U1") (pin "61") (pinfunction "PB8_61") (pintype "bidirectional"))
    )
    (net (code "87") (name "unconnected-(U1-PB9-Pad62)") (class "Default")
      (node (ref "U1") (pin "62") (pinfunction "PB9_62") (pintype "bidirectional"))
    )
    (net (code "88") (name "unconnected-(U1-PB10-Pad29)") (class "Default")
      (node (ref "U1") (pin "29") (pinfunction "PB10_29") (pintype "bidirectional"))
    )
    (net (code "89") (name "unconnected-(U1-PB11-Pad30)") (class "Default")
      (node (ref "U1") (pin "30") (pinfunction "PB11_30") (pintype "bidirectional"))
    )
    (net (code "90") (name "unconnected-(U1-PB12-Pad33)") (class "Default")
      (node (ref "U1") (pin "33") (pinfunction "PB12_33") (pintype "bidirectional"))
    )
    (net (code "91") (name "unconnected-(U1-PB15-Pad36)") (class "Default")
      (node (ref "U1") (pin "36") (pinfunction "PB15_36") (pintype "bidirectional"))
    )
    (net (code "92") (name "unconnected-(U1-PC0-Pad8)") (class "Default")
      (node (ref "U1") (pin "8") (pinfunction "PC0_8") (pintype "bidirectional"))
    )
    (net (code "93") (name "unconnected-(U1-PC2-Pad10)") (class "Default")
      (node (ref "U1") (pin "10") (pinfunction "PC2_10") (pintype "bidirectional"))
    )
    (net (code "94") (name "unconnected-(U1-PC3-Pad11)") (class "Default")
      (node (ref "U1") (pin "11") (pinfunction "PC3_11") (pintype "bidirectional"))
    )
    (net (code "95") (name "unconnected-(U1-PC5-Pad25)") (class "Default")
      (node (ref "U1") (pin "25") (pinfunction "PC5_25") (pintype "bidirectional"))
    )
    (net (code "96") (name "unconnected-(U1-PC8-Pad39)") (class "Default")
      (node (ref "U1") (pin "39") (pinfunction "PC8_39") (pintype "bidirectional"))
    )
    (net (code "97") (name "unconnected-(U1-PC10-Pad51)") (class "Default")
      (node (ref "U1") (pin "51") (pinfunction "PC10_51") (pintype "bidirectional"))
    )
    (net (code "98") (name "unconnected-(U1-PC11-Pad52)") (class "Default")
      (node (ref "U1") (pin "52") (pinfunction "PC11_52") (pintype "bidirectional"))
    )
    (net (code "99") (name "unconnected-(U1-PC12-Pad53)") (class "Default")
      (node (ref "U1") (pin "53") (pinfunction "PC12_53") (pintype "bidirectional"))
    )
    (net (code "100") (name "unconnected-(U1-PC13-Pad2)") (class "Default")
      (node (ref "U1") (pin "2") (pinfunction "PC13_2") (pintype "bidirectional"))
    )
    (net (code "101") (name "unconnected-(U1-PD2-Pad54)") (class "Default")
      (node (ref "U1") (pin "54") (pinfunction "PD2_54") (pintype "bidirectional"))
    )
    (net (code "102") (name "unconnected-(U1-PH1-OSC-OUT-Pad6)") (class "Default")
      (node (ref "U1") (pin "6") (pinfunction "PH1-OSC-OUT_6") (pintype "bidirectional"))
    )
  )
)
